# ina_extension_led_scheamtic.net
KiCad netlist of a schematic drawn in Altium Designer
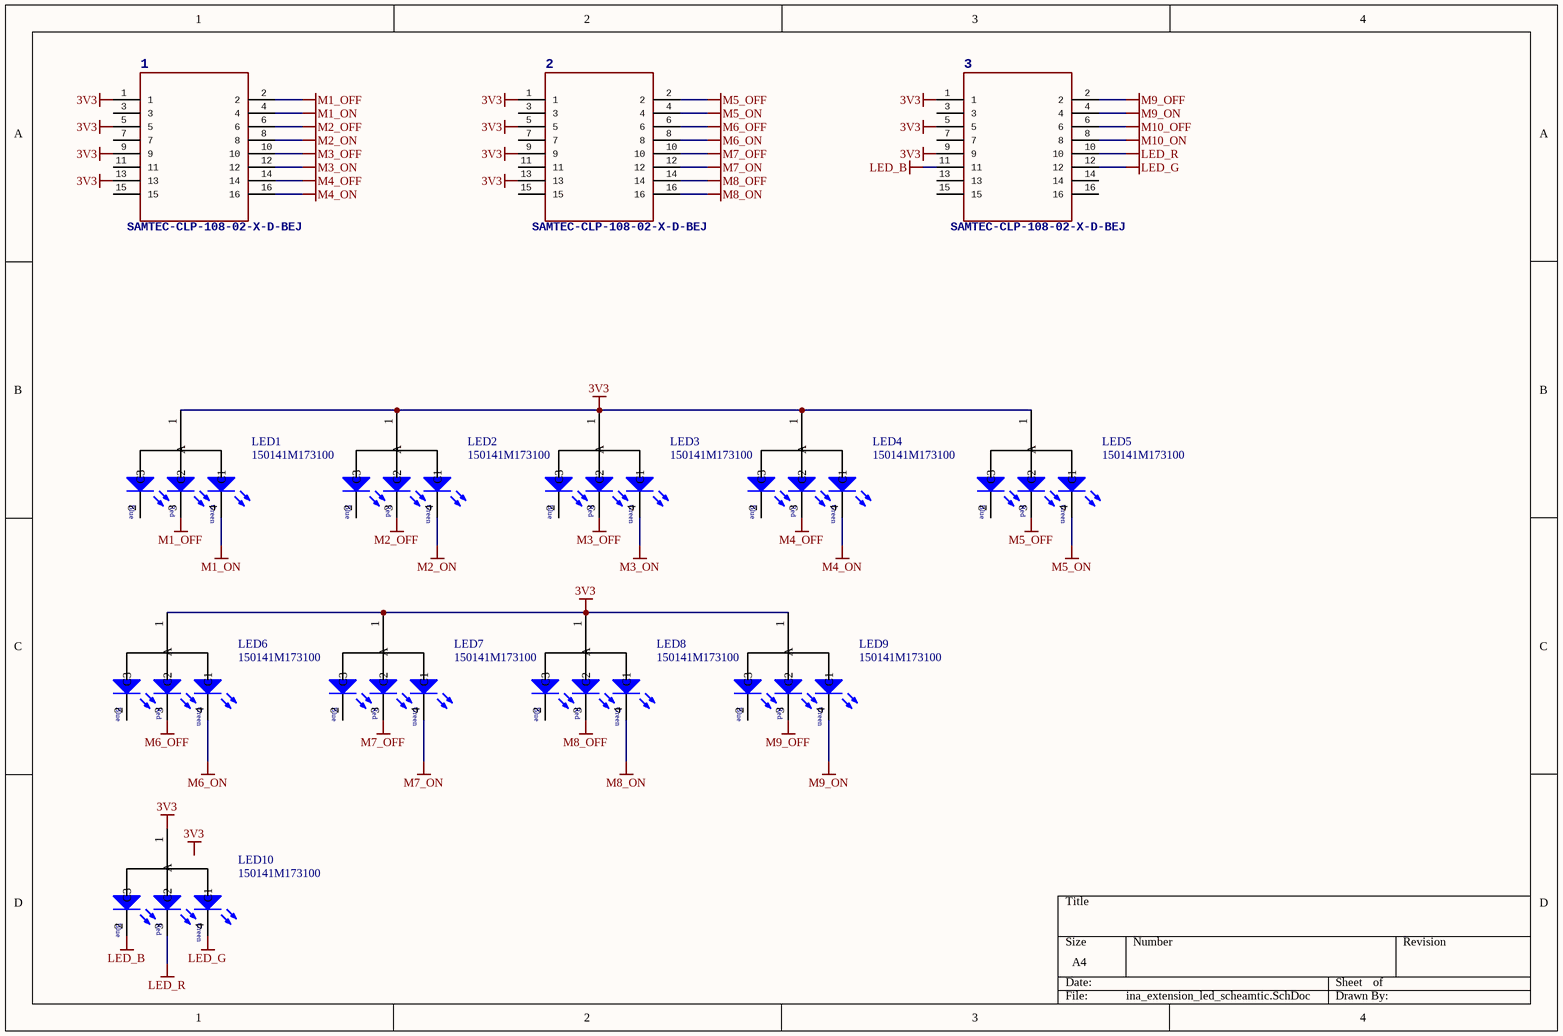
[diagram p0: ina_extension_led_scheamtic.SchDoc]

(export (version "E")
  (design (tool "Eeschema 10.0.6"))
  (components
    (comp (ref "1")
      (value "SAMTEC-CLP-108-02-X-D-BEJ")
      (footprint "SAMTEC-CLP-108-02-X-D-BE")
      (libsource (lib "SAMTEC-CLP-108-02-X-D-BE") (part "SAMTEC-CLP-108-02-X-D-BEJ"))
    )
    (comp (ref "2")
      (value "SAMTEC-CLP-108-02-X-D-BEJ")
      (footprint "SAMTEC-CLP-108-02-X-D-BE")
      (libsource (lib "SAMTEC-CLP-108-02-X-D-BE") (part "SAMTEC-CLP-108-02-X-D-BEJ"))
    )
    (comp (ref "3")
      (value "SAMTEC-CLP-108-02-X-D-BEJ")
      (footprint "SAMTEC-CLP-108-02-X-D-BE")
      (libsource (lib "SAMTEC-CLP-108-02-X-D-BE") (part "SAMTEC-CLP-108-02-X-D-BEJ"))
    )
    (comp (ref "LED1")
      (value "150141M173100")
      (footprint "LED RGB 3528")
      (description "SMD Full-Color Top LED, WL-SFTW, Red & Green & Blue")
      (fields
        (field (name "MANUFACTURER") "Würth Elektronik eiSos GmbH")
        (field (name "CREATED BY") "Christin Otto")
      )
      (libsource (lib "LIBRARY") (part "LED RGB SMD"))
    )
    (comp (ref "LED2")
      (value "150141M173100")
      (footprint "LED RGB 3528")
      (description "SMD Full-Color Top LED, WL-SFTW, Red & Green & Blue")
      (fields
        (field (name "MANUFACTURER") "Würth Elektronik eiSos GmbH")
        (field (name "CREATED BY") "Christin Otto")
      )
      (libsource (lib "LIBRARY") (part "LED RGB SMD"))
    )
    (comp (ref "LED3")
      (value "150141M173100")
      (footprint "LED RGB 3528")
      (description "SMD Full-Color Top LED, WL-SFTW, Red & Green & Blue")
      (fields
        (field (name "MANUFACTURER") "Würth Elektronik eiSos GmbH")
        (field (name "CREATED BY") "Christin Otto")
      )
      (libsource (lib "LIBRARY") (part "LED RGB SMD"))
    )
    (comp (ref "LED4")
      (value "150141M173100")
      (footprint "LED RGB 3528")
      (description "SMD Full-Color Top LED, WL-SFTW, Red & Green & Blue")
      (fields
        (field (name "MANUFACTURER") "Würth Elektronik eiSos GmbH")
        (field (name "CREATED BY") "Christin Otto")
      )
      (libsource (lib "LIBRARY") (part "LED RGB SMD"))
    )
    (comp (ref "LED5")
      (value "150141M173100")
      (footprint "LED RGB 3528")
      (description "SMD Full-Color Top LED, WL-SFTW, Red & Green & Blue")
      (fields
        (field (name "MANUFACTURER") "Würth Elektronik eiSos GmbH")
        (field (name "CREATED BY") "Christin Otto")
      )
      (libsource (lib "LIBRARY") (part "LED RGB SMD"))
    )
    (comp (ref "LED6")
      (value "150141M173100")
      (footprint "LED RGB 3528")
      (description "SMD Full-Color Top LED, WL-SFTW, Red & Green & Blue")
      (fields
        (field (name "MANUFACTURER") "Würth Elektronik eiSos GmbH")
        (field (name "CREATED BY") "Christin Otto")
      )
      (libsource (lib "LIBRARY") (part "LED RGB SMD"))
    )
    (comp (ref "LED7")
      (value "150141M173100")
      (footprint "LED RGB 3528")
      (description "SMD Full-Color Top LED, WL-SFTW, Red & Green & Blue")
      (fields
        (field (name "MANUFACTURER") "Würth Elektronik eiSos GmbH")
        (field (name "CREATED BY") "Christin Otto")
      )
      (libsource (lib "LIBRARY") (part "LED RGB SMD"))
    )
    (comp (ref "LED8")
      (value "150141M173100")
      (footprint "LED RGB 3528")
      (description "SMD Full-Color Top LED, WL-SFTW, Red & Green & Blue")
      (fields
        (field (name "MANUFACTURER") "Würth Elektronik eiSos GmbH")
        (field (name "CREATED BY") "Christin Otto")
      )
      (libsource (lib "LIBRARY") (part "LED RGB SMD"))
    )
    (comp (ref "LED9")
      (value "150141M173100")
      (footprint "LED RGB 3528")
      (description "SMD Full-Color Top LED, WL-SFTW, Red & Green & Blue")
      (fields
        (field (name "MANUFACTURER") "Würth Elektronik eiSos GmbH")
        (field (name "CREATED BY") "Christin Otto")
      )
      (libsource (lib "LIBRARY") (part "LED RGB SMD"))
    )
    (comp (ref "LED10")
      (value "150141M173100")
      (footprint "LED RGB 3528")
      (description "SMD Full-Color Top LED, WL-SFTW, Red & Green & Blue")
      (fields
        (field (name "MANUFACTURER") "Würth Elektronik eiSos GmbH")
        (field (name "CREATED BY") "Christin Otto")
      )
      (libsource (lib "LIBRARY") (part "LED RGB SMD"))
    )
  )
  (nets
    (net (code "1") (name "3V3") (class "Default")
      (node (ref "1") (pin "1") (pinfunction "1_1") (pintype "passive"))
      (node (ref "1") (pin "13") (pinfunction "13_13") (pintype "passive"))
      (node (ref "1") (pin "5") (pinfunction "5_5") (pintype "passive"))
      (node (ref "1") (pin "9") (pinfunction "9_9") (pintype "passive"))
      (node (ref "2") (pin "1") (pinfunction "1_1") (pintype "passive"))
      (node (ref "2") (pin "13") (pinfunction "13_13") (pintype "passive"))
      (node (ref "2") (pin "5") (pinfunction "5_5") (pintype "passive"))
      (node (ref "2") (pin "9") (pinfunction "9_9") (pintype "passive"))
      (node (ref "3") (pin "1") (pinfunction "1_1") (pintype "passive"))
      (node (ref "3") (pin "5") (pinfunction "5_5") (pintype "passive"))
      (node (ref "3") (pin "9") (pinfunction "9_9") (pintype "passive"))
      (node (ref "LED1") (pin "1") (pinfunction "A_1") (pintype "passive"))
      (node (ref "LED10") (pin "1") (pinfunction "A_1") (pintype "passive"))
      (node (ref "LED2") (pin "1") (pinfunction "A_1") (pintype "passive"))
      (node (ref "LED3") (pin "1") (pinfunction "A_1") (pintype "passive"))
      (node (ref "LED4") (pin "1") (pinfunction "A_1") (pintype "passive"))
      (node (ref "LED5") (pin "1") (pinfunction "A_1") (pintype "passive"))
      (node (ref "LED6") (pin "1") (pinfunction "A_1") (pintype "passive"))
      (node (ref "LED7") (pin "1") (pinfunction "A_1") (pintype "passive"))
      (node (ref "LED8") (pin "1") (pinfunction "A_1") (pintype "passive"))
      (node (ref "LED9") (pin "1") (pinfunction "A_1") (pintype "passive"))
    )
    (net (code "2") (name "LED_B") (class "Default")
      (node (ref "3") (pin "11") (pinfunction "11_11") (pintype "passive"))
      (node (ref "LED10") (pin "2") (pinfunction "C3_2") (pintype "passive"))
    )
    (net (code "3") (name "LED_G") (class "Default")
      (node (ref "3") (pin "12") (pinfunction "12_12") (pintype "passive"))
      (node (ref "LED10") (pin "4") (pinfunction "C1_4") (pintype "passive"))
    )
    (net (code "4") (name "LED_R") (class "Default")
      (node (ref "3") (pin "10") (pinfunction "10_10") (pintype "passive"))
      (node (ref "LED10") (pin "3") (pinfunction "C2_3") (pintype "passive"))
    )
    (net (code "5") (name "M1_OFF") (class "Default")
      (node (ref "1") (pin "2") (pinfunction "2_2") (pintype "passive"))
      (node (ref "LED1") (pin "3") (pinfunction "C2_3") (pintype "passive"))
    )
    (net (code "6") (name "M1_ON") (class "Default")
      (node (ref "1") (pin "4") (pinfunction "4_4") (pintype "passive"))
      (node (ref "LED1") (pin "4") (pinfunction "C1_4") (pintype "passive"))
    )
    (net (code "7") (name "M2_OFF") (class "Default")
      (node (ref "1") (pin "6") (pinfunction "6_6") (pintype "passive"))
      (node (ref "LED2") (pin "3") (pinfunction "C2_3") (pintype "passive"))
    )
    (net (code "8") (name "M2_ON") (class "Default")
      (node (ref "1") (pin "8") (pinfunction "8_8") (pintype "passive"))
      (node (ref "LED2") (pin "4") (pinfunction "C1_4") (pintype "passive"))
    )
    (net (code "9") (name "M3_OFF") (class "Default")
      (node (ref "1") (pin "10") (pinfunction "10_10") (pintype "passive"))
      (node (ref "LED3") (pin "3") (pinfunction "C2_3") (pintype "passive"))
    )
    (net (code "10") (name "M3_ON") (class "Default")
      (node (ref "1") (pin "12") (pinfunction "12_12") (pintype "passive"))
      (node (ref "LED3") (pin "4") (pinfunction "C1_4") (pintype "passive"))
    )
    (net (code "11") (name "M4_OFF") (class "Default")
      (node (ref "1") (pin "14") (pinfunction "14_14") (pintype "passive"))
      (node (ref "LED4") (pin "3") (pinfunction "C2_3") (pintype "passive"))
    )
    (net (code "12") (name "M4_ON") (class "Default")
      (node (ref "1") (pin "16") (pinfunction "16_16") (pintype "passive"))
      (node (ref "LED4") (pin "4") (pinfunction "C1_4") (pintype "passive"))
    )
    (net (code "13") (name "M5_OFF") (class "Default")
      (node (ref "2") (pin "2") (pinfunction "2_2") (pintype "passive"))
      (node (ref "LED5") (pin "3") (pinfunction "C2_3") (pintype "passive"))
    )
    (net (code "14") (name "M5_ON") (class "Default")
      (node (ref "2") (pin "4") (pinfunction "4_4") (pintype "passive"))
      (node (ref "LED5") (pin "4") (pinfunction "C1_4") (pintype "passive"))
    )
    (net (code "15") (name "M6_OFF") (class "Default")
      (node (ref "2") (pin "6") (pinfunction "6_6") (pintype "passive"))
      (node (ref "LED6") (pin "3") (pinfunction "C2_3") (pintype "passive"))
    )
    (net (code "16") (name "M6_ON") (class "Default")
      (node (ref "2") (pin "8") (pinfunction "8_8") (pintype "passive"))
      (node (ref "LED6") (pin "4") (pinfunction "C1_4") (pintype "passive"))
    )
    (net (code "17") (name "M7_OFF") (class "Default")
      (node (ref "2") (pin "10") (pinfunction "10_10") (pintype "passive"))
      (node (ref "LED7") (pin "3") (pinfunction "C2_3") (pintype "passive"))
    )
    (net (code "18") (name "M7_ON") (class "Default")
      (node (ref "2") (pin "12") (pinfunction "12_12") (pintype "passive"))
      (node (ref "LED7") (pin "4") (pinfunction "C1_4") (pintype "passive"))
    )
    (net (code "19") (name "M8_OFF") (class "Default")
      (node (ref "2") (pin "14") (pinfunction "14_14") (pintype "passive"))
      (node (ref "LED8") (pin "3") (pinfunction "C2_3") (pintype "passive"))
    )
    (net (code "20") (name "M8_ON") (class "Default")
      (node (ref "2") (pin "16") (pinfunction "16_16") (pintype "passive"))
      (node (ref "LED8") (pin "4") (pinfunction "C1_4") (pintype "passive"))
    )
    (net (code "21") (name "M9_OFF") (class "Default")
      (node (ref "3") (pin "2") (pinfunction "2_2") (pintype "passive"))
      (node (ref "LED9") (pin "3") (pinfunction "C2_3") (pintype "passive"))
    )
    (net (code "22") (name "M9_ON") (class "Default")
      (node (ref "3") (pin "4") (pinfunction "4_4") (pintype "passive"))
      (node (ref "LED9") (pin "4") (pinfunction "C1_4") (pintype "passive"))
    )
    (net (code "23") (name "M10_OFF") (class "Default")
      (node (ref "3") (pin "6") (pinfunction "6_6") (pintype "passive"))
    )
    (net (code "24") (name "M10_ON") (class "Default")
      (node (ref "3") (pin "8") (pinfunction "8_8") (pintype "passive"))
    )
    (net (code "25") (name "unconnected-(1-Pad3)") (class "Default")
      (node (ref "1") (pin "3") (pinfunction "3_3") (pintype "passive"))
    )
    (net (code "26") (name "unconnected-(1-Pad7)") (class "Default")
      (node (ref "1") (pin "7") (pinfunction "7_7") (pintype "passive"))
    )
    (net (code "27") (name "unconnected-(1-Pad11)") (class "Default")
      (node (ref "1") (pin "11") (pinfunction "11_11") (pintype "passive"))
    )
    (net (code "28") (name "unconnected-(1-Pad15)") (class "Default")
      (node (ref "1") (pin "15") (pinfunction "15_15") (pintype "passive"))
    )
    (net (code "29") (name "unconnected-(2-Pad3)") (class "Default")
      (node (ref "2") (pin "3") (pinfunction "3_3") (pintype "passive"))
    )
    (net (code "30") (name "unconnected-(2-Pad7)") (class "Default")
      (node (ref "2") (pin "7") (pinfunction "7_7") (pintype "passive"))
    )
    (net (code "31") (name "unconnected-(2-Pad11)") (class "Default")
      (node (ref "2") (pin "11") (pinfunction "11_11") (pintype "passive"))
    )
    (net (code "32") (name "unconnected-(2-Pad15)") (class "Default")
      (node (ref "2") (pin "15") (pinfunction "15_15") (pintype "passive"))
    )
    (net (code "33") (name "unconnected-(3-Pad3)") (class "Default")
      (node (ref "3") (pin "3") (pinfunction "3_3") (pintype "passive"))
    )
    (net (code "34") (name "unconnected-(3-Pad7)") (class "Default")
      (node (ref "3") (pin "7") (pinfunction "7_7") (pintype "passive"))
    )
    (net (code "35") (name "unconnected-(3-Pad13)") (class "Default")
      (node (ref "3") (pin "13") (pinfunction "13_13") (pintype "passive"))
    )
    (net (code "36") (name "unconnected-(3-Pad14)") (class "Default")
      (node (ref "3") (pin "14") (pinfunction "14_14") (pintype "passive"))
    )
    (net (code "37") (name "unconnected-(3-Pad15)") (class "Default")
      (node (ref "3") (pin "15") (pinfunction "15_15") (pintype "passive"))
    )
    (net (code "38") (name "unconnected-(3-Pad16)") (class "Default")
      (node (ref "3") (pin "16") (pinfunction "16_16") (pintype "passive"))
    )
    (net (code "39") (name "unconnected-(LED1-C3-Pad2)") (class "Default")
      (node (ref "LED1") (pin "2") (pinfunction "C3_2") (pintype "passive"))
    )
    (net (code "40") (name "unconnected-(LED2-C3-Pad2)") (class "Default")
      (node (ref "LED2") (pin "2") (pinfunction "C3_2") (pintype "passive"))
    )
    (net (code "41") (name "unconnected-(LED3-C3-Pad2)") (class "Default")
      (node (ref "LED3") (pin "2") (pinfunction "C3_2") (pintype "passive"))
    )
    (net (code "42") (name "unconnected-(LED4-C3-Pad2)") (class "Default")
      (node (ref "LED4") (pin "2") (pinfunction "C3_2") (pintype "passive"))
    )
    (net (code "43") (name "unconnected-(LED5-C3-Pad2)") (class "Default")
      (node (ref "LED5") (pin "2") (pinfunction "C3_2") (pintype "passive"))
    )
    (net (code "44") (name "unconnected-(LED6-C3-Pad2)") (class "Default")
      (node (ref "LED6") (pin "2") (pinfunction "C3_2") (pintype "passive"))
    )
    (net (code "45") (name "unconnected-(LED7-C3-Pad2)") (class "Default")
      (node (ref "LED7") (pin "2") (pinfunction "C3_2") (pintype "passive"))
    )
    (net (code "46") (name "unconnected-(LED8-C3-Pad2)") (class "Default")
      (node (ref "LED8") (pin "2") (pinfunction "C3_2") (pintype "passive"))
    )
    (net (code "47") (name "unconnected-(LED9-C3-Pad2)") (class "Default")
      (node (ref "LED9") (pin "2") (pinfunction "C3_2") (pintype "passive"))
    )
  )
)
